# sensor_array_interface.net
KiCad netlist of a schematic drawn in Altium Designer
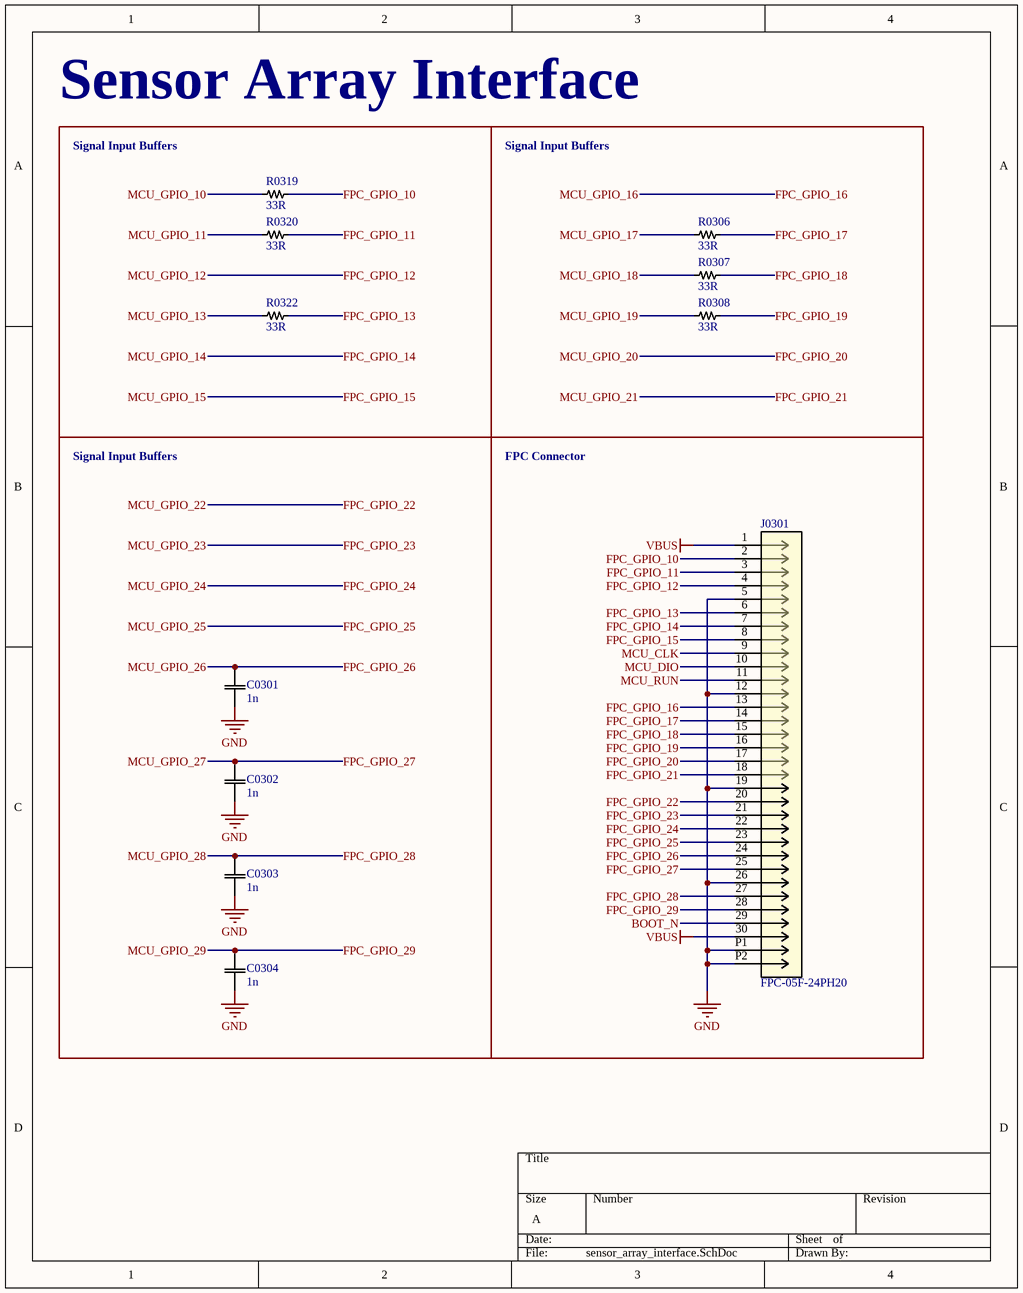
[diagram p0: sensor_array_interface.SchDoc]

(export (version "E")
  (design (tool "Eeschema 10.0.6"))
  (components
    (comp (ref "C0301")
      (value "1n")
      (footprint "CAPC10555_55N_KEM")
      (description "SMD Comm X7R, Ceramic, SMD, MLCC, Temperature Stable, 0402")
      (fields
        (field (name "MANUFACTURER_PART_NUMBER") "C0402C104K4RACTU")
        (field (name "COPYRIGHT") "Copyright (C) 2025 Ultra Librarian. All rights reserved.")
      )
      (libsource (lib "SplitHE_Int") (part "C0402"))
    )
    (comp (ref "C0302")
      (value "1n")
      (footprint "CAPC10555_55N_KEM")
      (description "SMD Comm X7R, Ceramic, SMD, MLCC, Temperature Stable, 0402")
      (fields
        (field (name "MANUFACTURER_PART_NUMBER") "C0402C104K4RACTU")
        (field (name "COPYRIGHT") "Copyright (C) 2025 Ultra Librarian. All rights reserved.")
      )
      (libsource (lib "SplitHE_Int") (part "C0402"))
    )
    (comp (ref "C0303")
      (value "1n")
      (footprint "CAPC10555_55N_KEM")
      (description "SMD Comm X7R, Ceramic, SMD, MLCC, Temperature Stable, 0402")
      (fields
        (field (name "MANUFACTURER_PART_NUMBER") "C0402C104K4RACTU")
        (field (name "COPYRIGHT") "Copyright (C) 2025 Ultra Librarian. All rights reserved.")
      )
      (libsource (lib "SplitHE_Int") (part "C0402"))
    )
    (comp (ref "C0304")
      (value "1n")
      (footprint "CAPC10555_55N_KEM")
      (description "SMD Comm X7R, Ceramic, SMD, MLCC, Temperature Stable, 0402")
      (fields
        (field (name "MANUFACTURER_PART_NUMBER") "C0402C104K4RACTU")
        (field (name "COPYRIGHT") "Copyright (C) 2025 Ultra Librarian. All rights reserved.")
      )
      (libsource (lib "SplitHE_Int") (part "C0402"))
    )
    (comp (ref "J0301")
      (value "FPC-05F-24PH20")
      (footprint "FPC-05F-30PH20")
      (description "24 Pin 0.5 Pitch FPC connector")
      (libsource (lib "SplitHE_Int") (part "FPC-05F-24PH20_1"))
    )
    (comp (ref "R0306")
      (value "33R")
      (footprint "RES0402_CPF_TYCO_TYC")
      (description "CPF 0402 RL")
      (fields
        (field (name "MANUFACTURER_PART_NUMBER") "CPF0402B33RE1")
        (field (name "COPYRIGHT") "Copyright (C) 2025 Ultra Librarian. All rights reserved.")
      )
      (libsource (lib "SplitHE_Int") (part "R0402"))
    )
    (comp (ref "R0307")
      (value "33R")
      (footprint "RES0402_CPF_TYCO_TYC")
      (description "CPF 0402 RL")
      (fields
        (field (name "MANUFACTURER_PART_NUMBER") "CPF0402B33RE1")
        (field (name "COPYRIGHT") "Copyright (C) 2025 Ultra Librarian. All rights reserved.")
      )
      (libsource (lib "SplitHE_Int") (part "R0402"))
    )
    (comp (ref "R0308")
      (value "33R")
      (footprint "RES0402_CPF_TYCO_TYC")
      (description "CPF 0402 RL")
      (fields
        (field (name "MANUFACTURER_PART_NUMBER") "CPF0402B33RE1")
        (field (name "COPYRIGHT") "Copyright (C) 2025 Ultra Librarian. All rights reserved.")
      )
      (libsource (lib "SplitHE_Int") (part "R0402"))
    )
    (comp (ref "R0319")
      (value "33R")
      (footprint "RES0402_CPF_TYCO_TYC")
      (description "CPF 0402 RL")
      (fields
        (field (name "MANUFACTURER_PART_NUMBER") "CPF0402B33RE1")
        (field (name "COPYRIGHT") "Copyright (C) 2025 Ultra Librarian. All rights reserved.")
      )
      (libsource (lib "SplitHE_Int") (part "R0402"))
    )
    (comp (ref "R0320")
      (value "33R")
      (footprint "RES0402_CPF_TYCO_TYC")
      (description "CPF 0402 RL")
      (fields
        (field (name "MANUFACTURER_PART_NUMBER") "CPF0402B33RE1")
        (field (name "COPYRIGHT") "Copyright (C) 2025 Ultra Librarian. All rights reserved.")
      )
      (libsource (lib "SplitHE_Int") (part "R0402"))
    )
    (comp (ref "R0322")
      (value "33R")
      (footprint "RES0402_CPF_TYCO_TYC")
      (description "CPF 0402 RL")
      (fields
        (field (name "MANUFACTURER_PART_NUMBER") "CPF0402B33RE1")
        (field (name "COPYRIGHT") "Copyright (C) 2025 Ultra Librarian. All rights reserved.")
      )
      (libsource (lib "SplitHE_Int") (part "R0402"))
    )
  )
  (nets
    (net (code "1") (name "/BOOT_N") (class "Default")
      (node (ref "J0301") (pin "29") (pinfunction "29_29") (pintype "passive"))
    )
    (net (code "2") (name "/FPC_GPIO_10") (class "Default")
      (node (ref "J0301") (pin "2") (pinfunction "2_2") (pintype "passive"))
      (node (ref "R0319") (pin "1") (pinfunction "1_1") (pintype "passive"))
    )
    (net (code "3") (name "/FPC_GPIO_11") (class "Default")
      (node (ref "J0301") (pin "3") (pinfunction "3_3") (pintype "passive"))
      (node (ref "R0320") (pin "1") (pinfunction "1_1") (pintype "passive"))
    )
    (net (code "4") (name "/FPC_GPIO_12") (class "Default")
      (node (ref "J0301") (pin "4") (pinfunction "4_4") (pintype "passive"))
    )
    (net (code "5") (name "/FPC_GPIO_13") (class "Default")
      (node (ref "J0301") (pin "6") (pinfunction "6_6") (pintype "passive"))
      (node (ref "R0322") (pin "1") (pinfunction "1_1") (pintype "passive"))
    )
    (net (code "6") (name "/FPC_GPIO_14") (class "Default")
      (node (ref "J0301") (pin "7") (pinfunction "7_7") (pintype "passive"))
    )
    (net (code "7") (name "/FPC_GPIO_15") (class "Default")
      (node (ref "J0301") (pin "8") (pinfunction "8_8") (pintype "passive"))
    )
    (net (code "8") (name "/FPC_GPIO_16") (class "Default")
      (node (ref "J0301") (pin "13") (pinfunction "13_13") (pintype "passive"))
    )
    (net (code "9") (name "/FPC_GPIO_17") (class "Default")
      (node (ref "J0301") (pin "14") (pinfunction "14_14") (pintype "passive"))
      (node (ref "R0306") (pin "1") (pinfunction "1_1") (pintype "passive"))
    )
    (net (code "10") (name "/FPC_GPIO_18") (class "Default")
      (node (ref "J0301") (pin "15") (pinfunction "15_15") (pintype "passive"))
      (node (ref "R0307") (pin "1") (pinfunction "1_1") (pintype "passive"))
    )
    (net (code "11") (name "/FPC_GPIO_19") (class "Default")
      (node (ref "J0301") (pin "16") (pinfunction "16_16") (pintype "passive"))
      (node (ref "R0308") (pin "1") (pinfunction "1_1") (pintype "passive"))
    )
    (net (code "12") (name "/FPC_GPIO_20") (class "Default")
      (node (ref "J0301") (pin "17") (pinfunction "17_17") (pintype "passive"))
    )
    (net (code "13") (name "/FPC_GPIO_21") (class "Default")
      (node (ref "J0301") (pin "18") (pinfunction "18_18") (pintype "passive"))
    )
    (net (code "14") (name "/FPC_GPIO_22") (class "Default")
      (node (ref "J0301") (pin "20") (pinfunction "20_20") (pintype "passive"))
    )
    (net (code "15") (name "/FPC_GPIO_23") (class "Default")
      (node (ref "J0301") (pin "21") (pinfunction "21_21") (pintype "passive"))
    )
    (net (code "16") (name "/FPC_GPIO_24") (class "Default")
      (node (ref "J0301") (pin "22") (pinfunction "22_22") (pintype "passive"))
    )
    (net (code "17") (name "/FPC_GPIO_25") (class "Default")
      (node (ref "J0301") (pin "23") (pinfunction "23_23") (pintype "passive"))
    )
    (net (code "18") (name "/FPC_GPIO_26") (class "Default")
      (node (ref "C0301") (pin "2") (pinfunction "2_2") (pintype "passive"))
      (node (ref "J0301") (pin "24") (pinfunction "24_24") (pintype "passive"))
    )
    (net (code "19") (name "/FPC_GPIO_27") (class "Default")
      (node (ref "C0302") (pin "2") (pinfunction "2_2") (pintype "passive"))
      (node (ref "J0301") (pin "25") (pinfunction "25_25") (pintype "passive"))
    )
    (net (code "20") (name "/FPC_GPIO_28") (class "Default")
      (node (ref "C0303") (pin "2") (pinfunction "2_2") (pintype "passive"))
      (node (ref "J0301") (pin "27") (pinfunction "27_27") (pintype "passive"))
    )
    (net (code "21") (name "/FPC_GPIO_29") (class "Default")
      (node (ref "C0304") (pin "2") (pinfunction "2_2") (pintype "passive"))
      (node (ref "J0301") (pin "28") (pinfunction "28_28") (pintype "passive"))
    )
    (net (code "22") (name "/MCU_CLK") (class "Default")
      (node (ref "J0301") (pin "9") (pinfunction "9_9") (pintype "passive"))
    )
    (net (code "23") (name "/MCU_DIO") (class "Default")
      (node (ref "J0301") (pin "10") (pinfunction "10_10") (pintype "passive"))
    )
    (net (code "24") (name "/MCU_GPIO_10") (class "Default")
      (node (ref "R0319") (pin "2") (pinfunction "2_2") (pintype "passive"))
    )
    (net (code "25") (name "/MCU_GPIO_11") (class "Default")
      (node (ref "R0320") (pin "2") (pinfunction "2_2") (pintype "passive"))
    )
    (net (code "26") (name "/MCU_GPIO_13") (class "Default")
      (node (ref "R0322") (pin "2") (pinfunction "2_2") (pintype "passive"))
    )
    (net (code "27") (name "/MCU_GPIO_17") (class "Default")
      (node (ref "R0306") (pin "2") (pinfunction "2_2") (pintype "passive"))
    )
    (net (code "28") (name "/MCU_GPIO_18") (class "Default")
      (node (ref "R0307") (pin "2") (pinfunction "2_2") (pintype "passive"))
    )
    (net (code "29") (name "/MCU_GPIO_19") (class "Default")
      (node (ref "R0308") (pin "2") (pinfunction "2_2") (pintype "passive"))
    )
    (net (code "30") (name "/MCU_RUN") (class "Default")
      (node (ref "J0301") (pin "11") (pinfunction "11_11") (pintype "passive"))
    )
    (net (code "31") (name "GND") (class "Default")
      (node (ref "C0301") (pin "1") (pinfunction "1_1") (pintype "passive"))
      (node (ref "C0302") (pin "1") (pinfunction "1_1") (pintype "passive"))
      (node (ref "C0303") (pin "1") (pinfunction "1_1") (pintype "passive"))
      (node (ref "C0304") (pin "1") (pinfunction "1_1") (pintype "passive"))
      (node (ref "J0301") (pin "12") (pinfunction "12_12") (pintype "passive"))
      (node (ref "J0301") (pin "19") (pinfunction "19_19") (pintype "passive"))
      (node (ref "J0301") (pin "26") (pinfunction "26_26") (pintype "passive"))
      (node (ref "J0301") (pin "5") (pinfunction "5_5") (pintype "passive"))
      (node (ref "J0301") (pin "P1") (pinfunction "P1_P1") (pintype "passive"))
      (node (ref "J0301") (pin "P2") (pinfunction "P2_P2") (pintype "passive"))
    )
    (net (code "32") (name "VBUS") (class "Default")
      (node (ref "J0301") (pin "1") (pinfunction "1_1") (pintype "passive"))
      (node (ref "J0301") (pin "30") (pinfunction "30_30") (pintype "passive"))
    )
  )
)
